# 16n.net
KiCad netlist of a schematic drawn in EAGLE
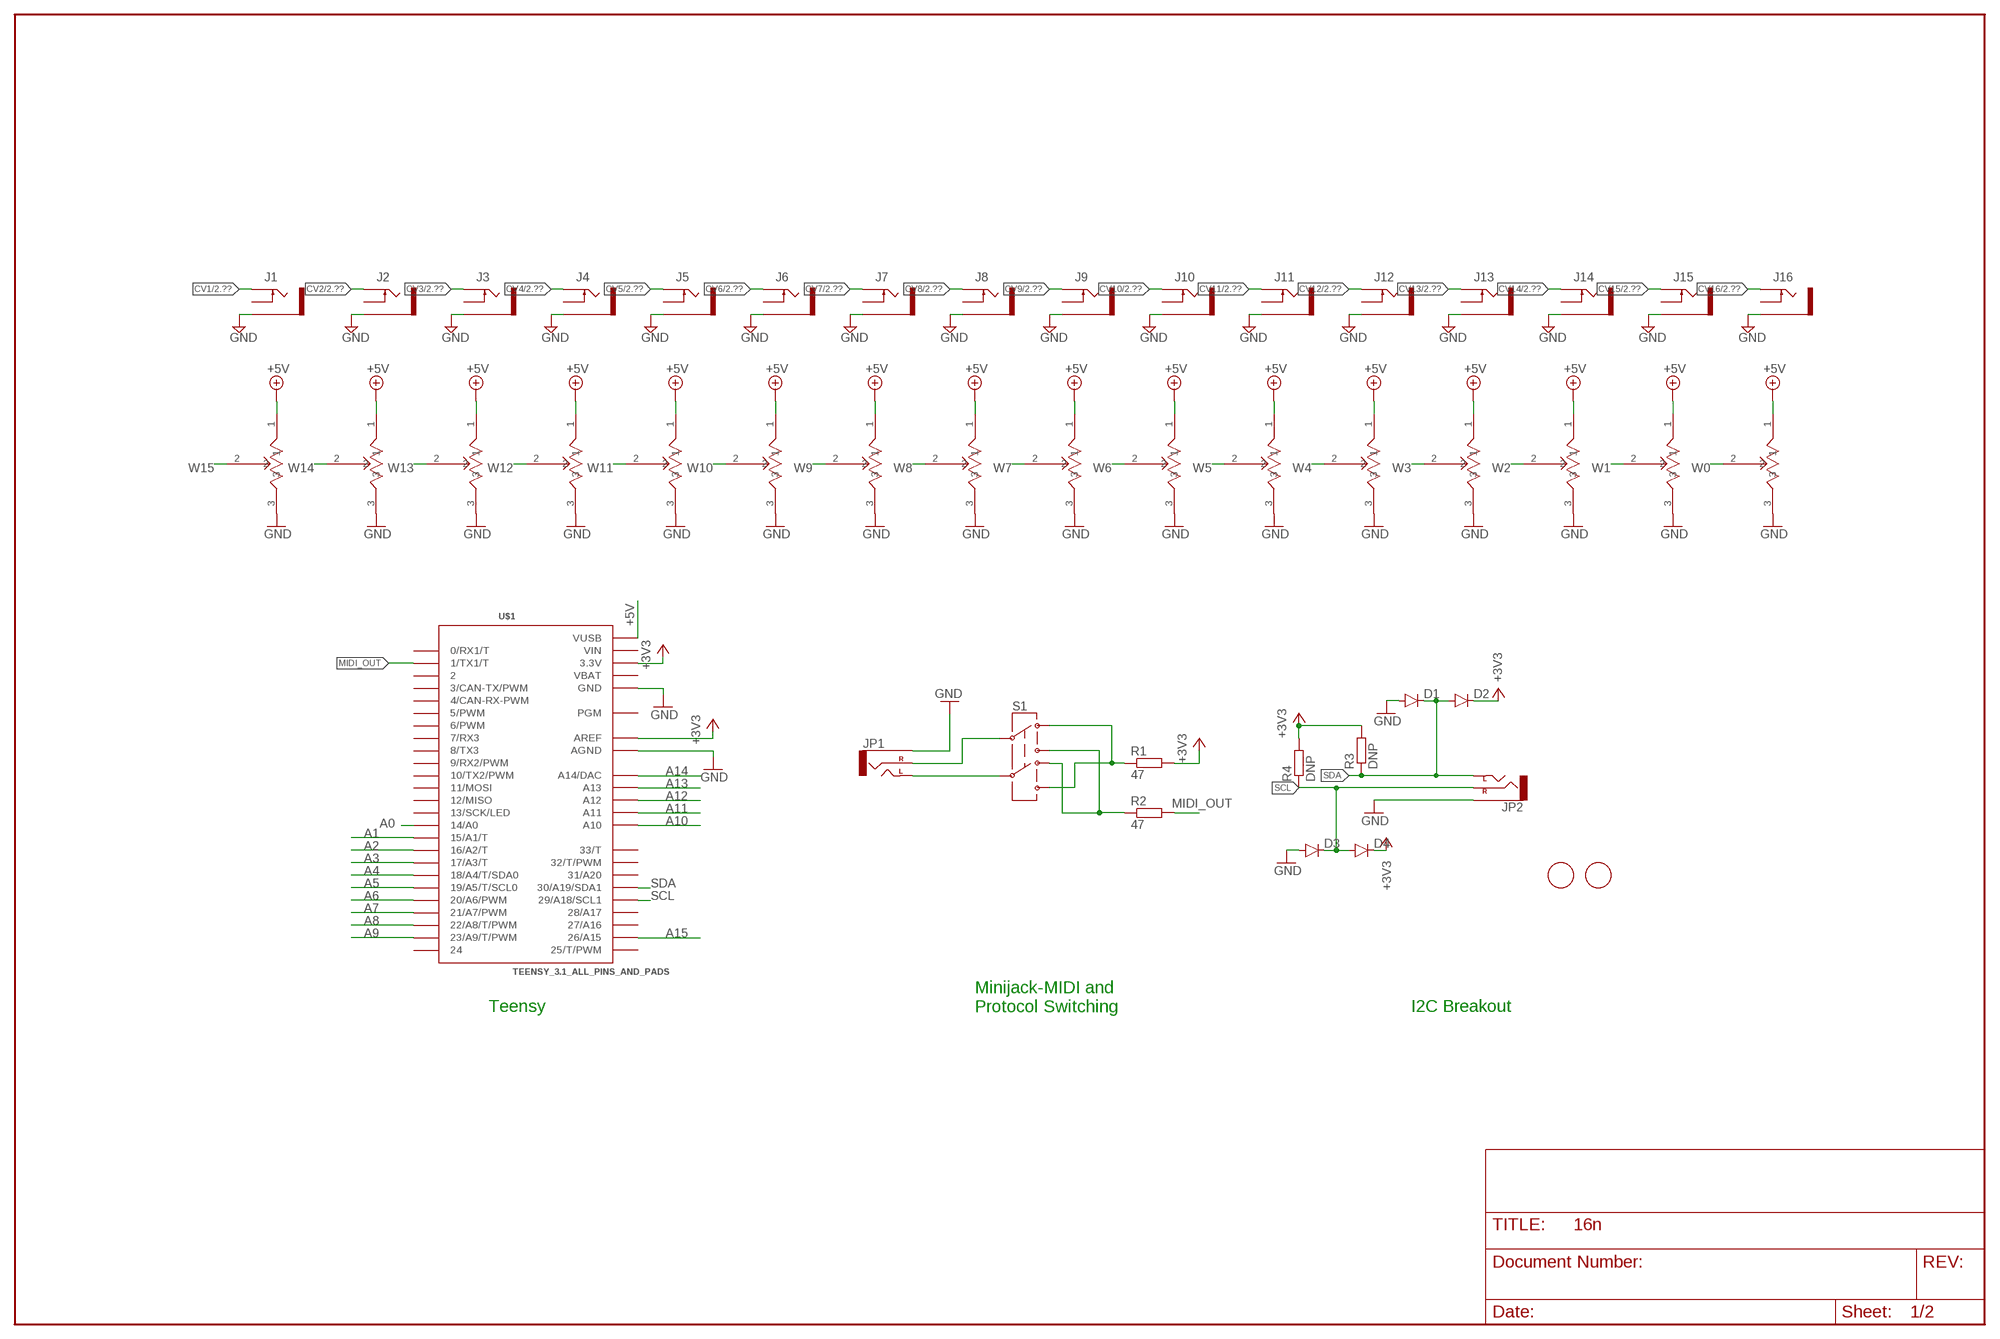
[diagram p0: schematic, sheet 1]
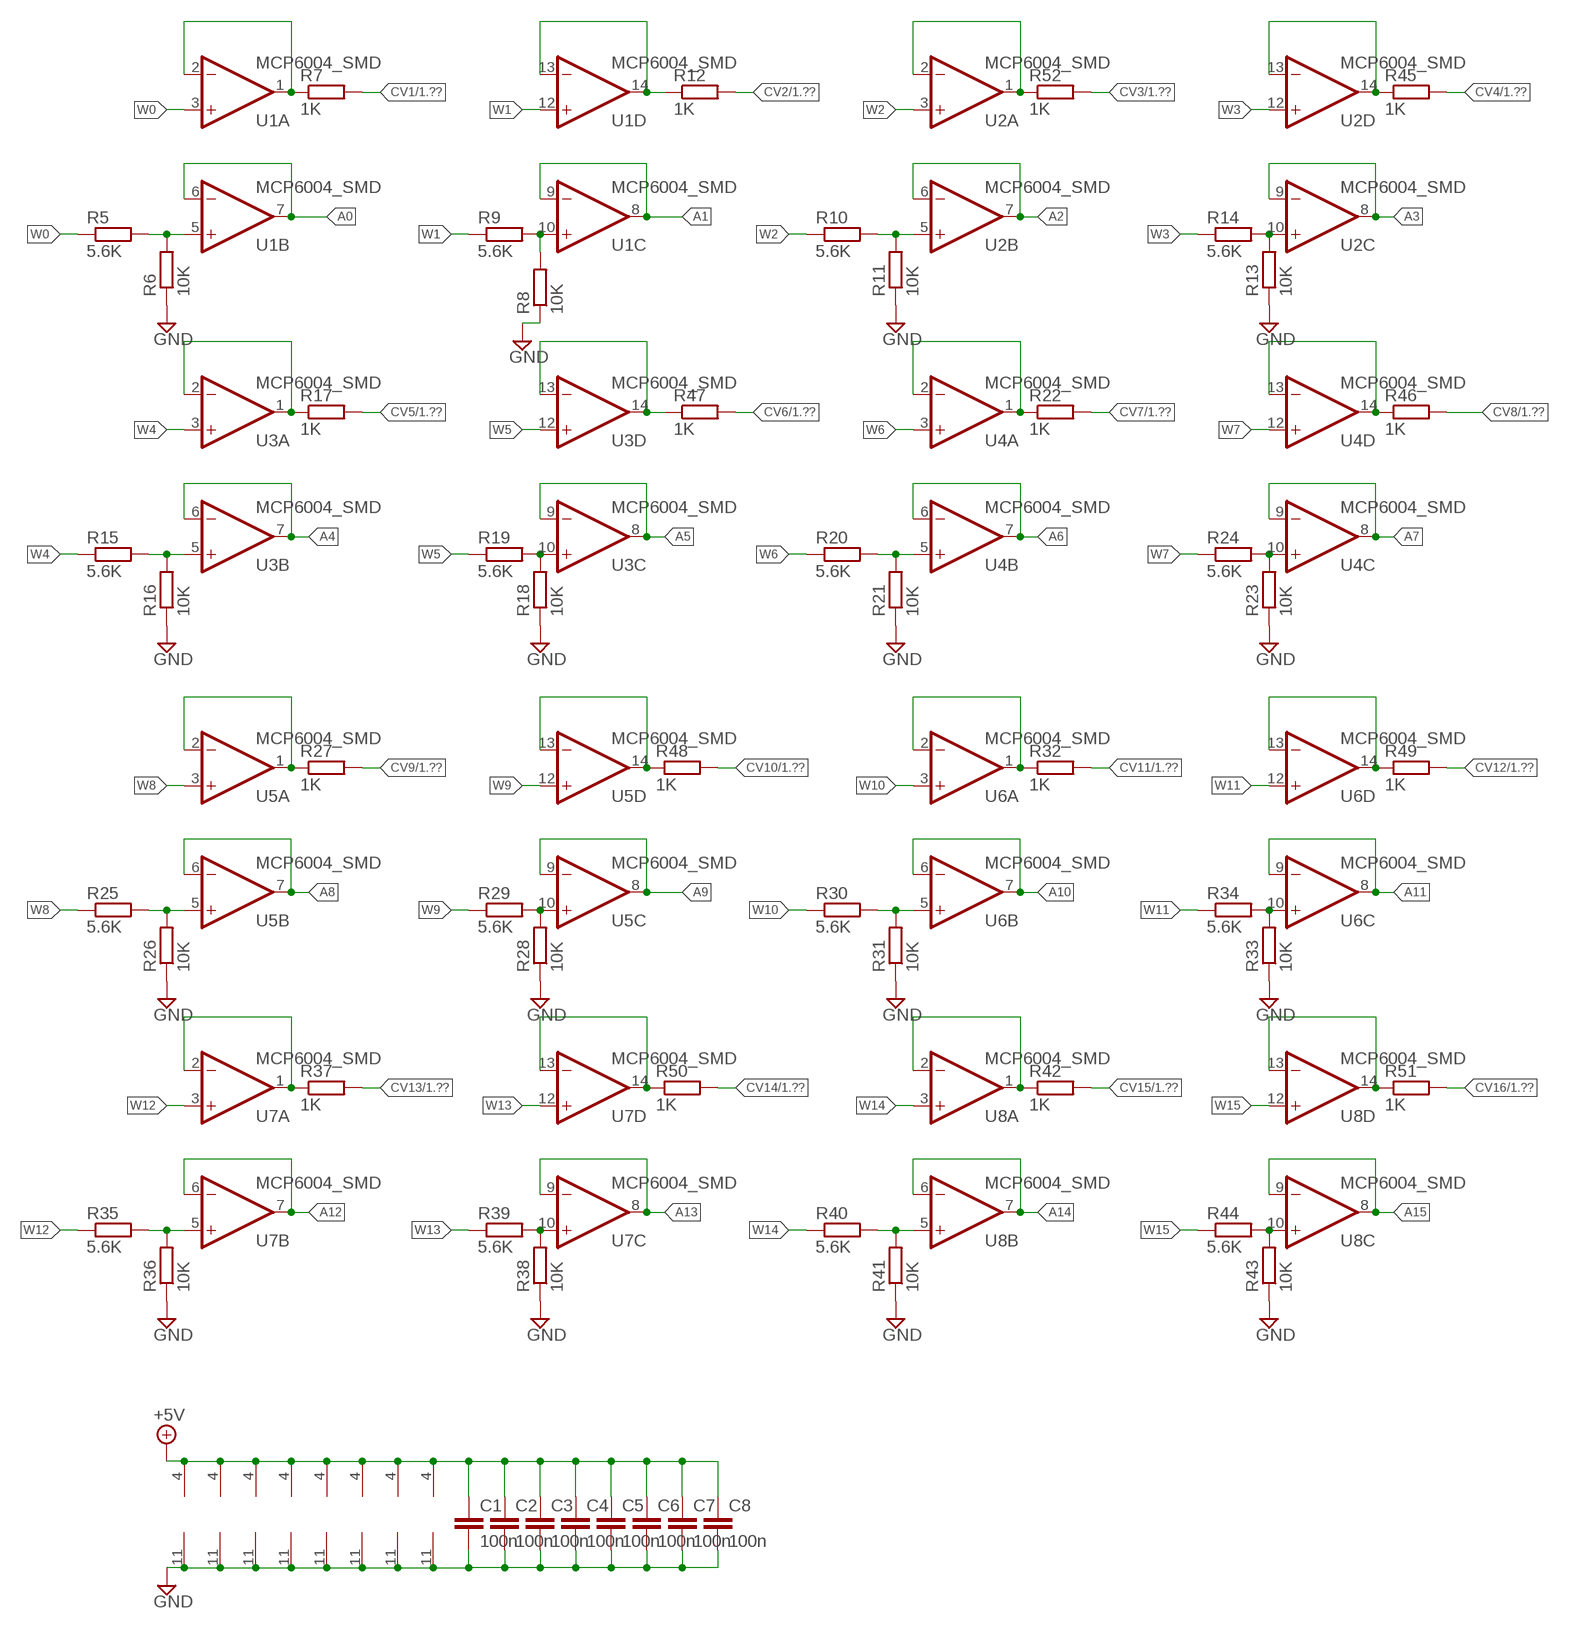
[diagram p1: schematic, sheet 2]

(export (version "E")
  (design (tool "Eeschema 10.0.6"))
  (components
    (comp (ref "D1")
      (value "DIODESOD123")
      (footprint "eagle-import:SOD-123")
      (libsource (lib "eagle-import") (part "DIODESOD123"))
    )
    (comp (ref "D2")
      (value "DIODESOD123")
      (footprint "eagle-import:SOD-123")
      (libsource (lib "eagle-import") (part "DIODESOD123"))
    )
    (comp (ref "D3")
      (value "DIODESOD123")
      (footprint "eagle-import:SOD-123")
      (libsource (lib "eagle-import") (part "DIODESOD123"))
    )
    (comp (ref "D4")
      (value "DIODESOD123")
      (footprint "eagle-import:SOD-123")
      (libsource (lib "eagle-import") (part "DIODESOD123"))
    )
    (comp (ref "FID1")
      (value "FIDUCIAL")
      (footprint "eagle-import:FIDUCIAL_1MM")
      (libsource (lib "eagle-import") (part "FIDUCIAL"))
    )
    (comp (ref "FID2")
      (value "FIDUCIAL")
      (footprint "eagle-import:FIDUCIAL_1MM")
      (libsource (lib "eagle-import") (part "FIDUCIAL"))
    )
    (comp (ref "J1")
      (value "PJ302M")
      (footprint "eagle-import:PJ302M")
      (libsource (lib "eagle-import") (part "PJ302M"))
    )
    (comp (ref "J2")
      (value "PJ302M")
      (footprint "eagle-import:PJ302M")
      (libsource (lib "eagle-import") (part "PJ302M"))
    )
    (comp (ref "J3")
      (value "PJ302M")
      (footprint "eagle-import:PJ302M")
      (libsource (lib "eagle-import") (part "PJ302M"))
    )
    (comp (ref "J4")
      (value "PJ302M")
      (footprint "eagle-import:PJ302M")
      (libsource (lib "eagle-import") (part "PJ302M"))
    )
    (comp (ref "J5")
      (value "PJ302M")
      (footprint "eagle-import:PJ302M")
      (libsource (lib "eagle-import") (part "PJ302M"))
    )
    (comp (ref "J6")
      (value "PJ302M")
      (footprint "eagle-import:PJ302M")
      (libsource (lib "eagle-import") (part "PJ302M"))
    )
    (comp (ref "J7")
      (value "PJ302M")
      (footprint "eagle-import:PJ302M")
      (libsource (lib "eagle-import") (part "PJ302M"))
    )
    (comp (ref "J8")
      (value "PJ302M")
      (footprint "eagle-import:PJ302M")
      (libsource (lib "eagle-import") (part "PJ302M"))
    )
    (comp (ref "J9")
      (value "PJ302M")
      (footprint "eagle-import:PJ302M")
      (libsource (lib "eagle-import") (part "PJ302M"))
    )
    (comp (ref "J10")
      (value "PJ302M")
      (footprint "eagle-import:PJ302M")
      (libsource (lib "eagle-import") (part "PJ302M"))
    )
    (comp (ref "J11")
      (value "PJ302M")
      (footprint "eagle-import:PJ302M")
      (libsource (lib "eagle-import") (part "PJ302M"))
    )
    (comp (ref "J12")
      (value "PJ302M")
      (footprint "eagle-import:PJ302M")
      (libsource (lib "eagle-import") (part "PJ302M"))
    )
    (comp (ref "J13")
      (value "PJ302M")
      (footprint "eagle-import:PJ302M")
      (libsource (lib "eagle-import") (part "PJ302M"))
    )
    (comp (ref "J14")
      (value "PJ302M")
      (footprint "eagle-import:PJ302M")
      (libsource (lib "eagle-import") (part "PJ302M"))
    )
    (comp (ref "J15")
      (value "PJ302M")
      (footprint "eagle-import:PJ302M")
      (libsource (lib "eagle-import") (part "PJ302M"))
    )
    (comp (ref "J16")
      (value "PJ302M")
      (footprint "eagle-import:PJ302M")
      (libsource (lib "eagle-import") (part "PJ302M"))
    )
    (comp (ref "JP1")
      (value "AUDIO-JACKPTH")
      (footprint "eagle-import:AUDIO-JACK")
      (libsource (lib "eagle-import") (part "AUDIO-JACKPTH"))
    )
    (comp (ref "JP2")
      (value "AUDIO-JACKPTH")
      (footprint "eagle-import:AUDIO-JACK")
      (libsource (lib "eagle-import") (part "AUDIO-JACKPTH"))
    )
    (comp (ref "R1")
      (value "47")
      (footprint "eagle-import:R0805")
      (libsource (lib "eagle-import") (part "R-EU_R0805"))
    )
    (comp (ref "R2")
      (value "47")
      (footprint "eagle-import:R0805")
      (libsource (lib "eagle-import") (part "R-EU_R0805"))
    )
    (comp (ref "R3")
      (value "DNP")
      (footprint "eagle-import:R0805")
      (libsource (lib "eagle-import") (part "R-EU_R0805"))
    )
    (comp (ref "R4")
      (value "DNP")
      (footprint "eagle-import:R0805")
      (libsource (lib "eagle-import") (part "R-EU_R0805"))
    )
    (comp (ref "S1")
      (value "SWITCH-DPDTEG2211")
      (footprint "eagle-import:EG2211")
      (libsource (lib "eagle-import") (part "SWITCH-DPDTEG2211"))
    )
    (comp (ref "U$1")
      (value "TEENSY_3.1_ALL_PINS_AND_PADS")
      (footprint "eagle-import:TEENSY_3.1_ALLPINS")
      (libsource (lib "eagle-import") (part "TEENSY_3.1_ALL_PINS_AND_PADS"))
    )
    (comp (ref "U$2")
      (value "SLIDEPOT-ALPS-60MM")
      (footprint "eagle-import:RS6011SP600")
      (libsource (lib "eagle-import") (part "SLIDEPOT-ALPS-60MM"))
    )
    (comp (ref "U$3")
      (value "SLIDEPOT-ALPS-60MM")
      (footprint "eagle-import:RS6011SP600")
      (libsource (lib "eagle-import") (part "SLIDEPOT-ALPS-60MM"))
    )
    (comp (ref "U$4")
      (value "SLIDEPOT-ALPS-60MM")
      (footprint "eagle-import:RS6011SP600")
      (libsource (lib "eagle-import") (part "SLIDEPOT-ALPS-60MM"))
    )
    (comp (ref "U$5")
      (value "SLIDEPOT-ALPS-60MM")
      (footprint "eagle-import:RS6011SP600")
      (libsource (lib "eagle-import") (part "SLIDEPOT-ALPS-60MM"))
    )
    (comp (ref "U$6")
      (value "SLIDEPOT-ALPS-60MM")
      (footprint "eagle-import:RS6011SP600")
      (libsource (lib "eagle-import") (part "SLIDEPOT-ALPS-60MM"))
    )
    (comp (ref "U$7")
      (value "SLIDEPOT-ALPS-60MM")
      (footprint "eagle-import:RS6011SP600")
      (libsource (lib "eagle-import") (part "SLIDEPOT-ALPS-60MM"))
    )
    (comp (ref "U$8")
      (value "SLIDEPOT-ALPS-60MM")
      (footprint "eagle-import:RS6011SP600")
      (libsource (lib "eagle-import") (part "SLIDEPOT-ALPS-60MM"))
    )
    (comp (ref "U$9")
      (value "SLIDEPOT-ALPS-60MM")
      (footprint "eagle-import:RS6011SP600")
      (libsource (lib "eagle-import") (part "SLIDEPOT-ALPS-60MM"))
    )
    (comp (ref "U$10")
      (value "SLIDEPOT-ALPS-60MM")
      (footprint "eagle-import:RS6011SP600")
      (libsource (lib "eagle-import") (part "SLIDEPOT-ALPS-60MM"))
    )
    (comp (ref "U$11")
      (value "SLIDEPOT-ALPS-60MM")
      (footprint "eagle-import:RS6011SP600")
      (libsource (lib "eagle-import") (part "SLIDEPOT-ALPS-60MM"))
    )
    (comp (ref "U$12")
      (value "SLIDEPOT-ALPS-60MM")
      (footprint "eagle-import:RS6011SP600")
      (libsource (lib "eagle-import") (part "SLIDEPOT-ALPS-60MM"))
    )
    (comp (ref "U$13")
      (value "SLIDEPOT-ALPS-60MM")
      (footprint "eagle-import:RS6011SP600")
      (libsource (lib "eagle-import") (part "SLIDEPOT-ALPS-60MM"))
    )
    (comp (ref "U$14")
      (value "SLIDEPOT-ALPS-60MM")
      (footprint "eagle-import:RS6011SP600")
      (libsource (lib "eagle-import") (part "SLIDEPOT-ALPS-60MM"))
    )
    (comp (ref "U$15")
      (value "SLIDEPOT-ALPS-60MM")
      (footprint "eagle-import:RS6011SP600")
      (libsource (lib "eagle-import") (part "SLIDEPOT-ALPS-60MM"))
    )
    (comp (ref "U$16")
      (value "SLIDEPOT-ALPS-60MM")
      (footprint "eagle-import:RS6011SP600")
      (libsource (lib "eagle-import") (part "SLIDEPOT-ALPS-60MM"))
    )
    (comp (ref "U$17")
      (value "SLIDEPOT-ALPS-60MM")
      (footprint "eagle-import:RS6011SP600")
      (libsource (lib "eagle-import") (part "SLIDEPOT-ALPS-60MM"))
    )
    (comp (ref "C1")
      (value "100n")
      (footprint "eagle-import:C0805")
      (libsource (lib "eagle-import") (part "C-EUC0805"))
    )
    (comp (ref "C2")
      (value "100n")
      (footprint "eagle-import:C0805")
      (libsource (lib "eagle-import") (part "C-EUC0805"))
    )
    (comp (ref "C3")
      (value "100n")
      (footprint "eagle-import:C0805")
      (libsource (lib "eagle-import") (part "C-EUC0805"))
    )
    (comp (ref "C4")
      (value "100n")
      (footprint "eagle-import:C0805")
      (libsource (lib "eagle-import") (part "C-EUC0805"))
    )
    (comp (ref "C5")
      (value "100n")
      (footprint "eagle-import:C0805")
      (libsource (lib "eagle-import") (part "C-EUC0805"))
    )
    (comp (ref "C6")
      (value "100n")
      (footprint "eagle-import:C0805")
      (libsource (lib "eagle-import") (part "C-EUC0805"))
    )
    (comp (ref "C7")
      (value "100n")
      (footprint "eagle-import:C0805")
      (libsource (lib "eagle-import") (part "C-EUC0805"))
    )
    (comp (ref "C8")
      (value "100n")
      (footprint "eagle-import:C0805")
      (libsource (lib "eagle-import") (part "C-EUC0805"))
    )
    (comp (ref "R5")
      (value "5.6K")
      (footprint "eagle-import:R0805")
      (libsource (lib "eagle-import") (part "R-EU_R0805"))
    )
    (comp (ref "R6")
      (value "10K")
      (footprint "eagle-import:R0805")
      (libsource (lib "eagle-import") (part "R-EU_R0805"))
    )
    (comp (ref "R7")
      (value "1K")
      (footprint "eagle-import:R0805")
      (libsource (lib "eagle-import") (part "R-EU_R0805"))
    )
    (comp (ref "R8")
      (value "10K")
      (footprint "eagle-import:R0805")
      (libsource (lib "eagle-import") (part "R-EU_R0805"))
    )
    (comp (ref "R9")
      (value "5.6K")
      (footprint "eagle-import:R0805")
      (libsource (lib "eagle-import") (part "R-EU_R0805"))
    )
    (comp (ref "R10")
      (value "5.6K")
      (footprint "eagle-import:R0805")
      (libsource (lib "eagle-import") (part "R-EU_R0805"))
    )
    (comp (ref "R11")
      (value "10K")
      (footprint "eagle-import:R0805")
      (libsource (lib "eagle-import") (part "R-EU_R0805"))
    )
    (comp (ref "R12")
      (value "1K")
      (footprint "eagle-import:R0805")
      (libsource (lib "eagle-import") (part "R-EU_R0805"))
    )
    (comp (ref "R13")
      (value "10K")
      (footprint "eagle-import:R0805")
      (libsource (lib "eagle-import") (part "R-EU_R0805"))
    )
    (comp (ref "R14")
      (value "5.6K")
      (footprint "eagle-import:R0805")
      (libsource (lib "eagle-import") (part "R-EU_R0805"))
    )
    (comp (ref "R15")
      (value "5.6K")
      (footprint "eagle-import:R0805")
      (libsource (lib "eagle-import") (part "R-EU_R0805"))
    )
    (comp (ref "R16")
      (value "10K")
      (footprint "eagle-import:R0805")
      (libsource (lib "eagle-import") (part "R-EU_R0805"))
    )
    (comp (ref "R17")
      (value "1K")
      (footprint "eagle-import:R0805")
      (libsource (lib "eagle-import") (part "R-EU_R0805"))
    )
    (comp (ref "R18")
      (value "10K")
      (footprint "eagle-import:R0805")
      (libsource (lib "eagle-import") (part "R-EU_R0805"))
    )
    (comp (ref "R19")
      (value "5.6K")
      (footprint "eagle-import:R0805")
      (libsource (lib "eagle-import") (part "R-EU_R0805"))
    )
    (comp (ref "R20")
      (value "5.6K")
      (footprint "eagle-import:R0805")
      (libsource (lib "eagle-import") (part "R-EU_R0805"))
    )
    (comp (ref "R21")
      (value "10K")
      (footprint "eagle-import:R0805")
      (libsource (lib "eagle-import") (part "R-EU_R0805"))
    )
    (comp (ref "R22")
      (value "1K")
      (footprint "eagle-import:R0805")
      (libsource (lib "eagle-import") (part "R-EU_R0805"))
    )
    (comp (ref "R23")
      (value "10K")
      (footprint "eagle-import:R0805")
      (libsource (lib "eagle-import") (part "R-EU_R0805"))
    )
    (comp (ref "R24")
      (value "5.6K")
      (footprint "eagle-import:R0805")
      (libsource (lib "eagle-import") (part "R-EU_R0805"))
    )
    (comp (ref "R25")
      (value "5.6K")
      (footprint "eagle-import:R0805")
      (libsource (lib "eagle-import") (part "R-EU_R0805"))
    )
    (comp (ref "R26")
      (value "10K")
      (footprint "eagle-import:R0805")
      (libsource (lib "eagle-import") (part "R-EU_R0805"))
    )
    (comp (ref "R27")
      (value "1K")
      (footprint "eagle-import:R0805")
      (libsource (lib "eagle-import") (part "R-EU_R0805"))
    )
    (comp (ref "R28")
      (value "10K")
      (footprint "eagle-import:R0805")
      (libsource (lib "eagle-import") (part "R-EU_R0805"))
    )
    (comp (ref "R29")
      (value "5.6K")
      (footprint "eagle-import:R0805")
      (libsource (lib "eagle-import") (part "R-EU_R0805"))
    )
    (comp (ref "R30")
      (value "5.6K")
      (footprint "eagle-import:R0805")
      (libsource (lib "eagle-import") (part "R-EU_R0805"))
    )
    (comp (ref "R31")
      (value "10K")
      (footprint "eagle-import:R0805")
      (libsource (lib "eagle-import") (part "R-EU_R0805"))
    )
    (comp (ref "R32")
      (value "1K")
      (footprint "eagle-import:R0805")
      (libsource (lib "eagle-import") (part "R-EU_R0805"))
    )
    (comp (ref "R33")
      (value "10K")
      (footprint "eagle-import:R0805")
      (libsource (lib "eagle-import") (part "R-EU_R0805"))
    )
    (comp (ref "R34")
      (value "5.6K")
      (footprint "eagle-import:R0805")
      (libsource (lib "eagle-import") (part "R-EU_R0805"))
    )
    (comp (ref "R35")
      (value "5.6K")
      (footprint "eagle-import:R0805")
      (libsource (lib "eagle-import") (part "R-EU_R0805"))
    )
    (comp (ref "R36")
      (value "10K")
      (footprint "eagle-import:R0805")
      (libsource (lib "eagle-import") (part "R-EU_R0805"))
    )
    (comp (ref "R37")
      (value "1K")
      (footprint "eagle-import:R0805")
      (libsource (lib "eagle-import") (part "R-EU_R0805"))
    )
    (comp (ref "R38")
      (value "10K")
      (footprint "eagle-import:R0805")
      (libsource (lib "eagle-import") (part "R-EU_R0805"))
    )
    (comp (ref "R39")
      (value "5.6K")
      (footprint "eagle-import:R0805")
      (libsource (lib "eagle-import") (part "R-EU_R0805"))
    )
    (comp (ref "R40")
      (value "5.6K")
      (footprint "eagle-import:R0805")
      (libsource (lib "eagle-import") (part "R-EU_R0805"))
    )
    (comp (ref "R41")
      (value "10K")
      (footprint "eagle-import:R0805")
      (libsource (lib "eagle-import") (part "R-EU_R0805"))
    )
    (comp (ref "R42")
      (value "1K")
      (footprint "eagle-import:R0805")
      (libsource (lib "eagle-import") (part "R-EU_R0805"))
    )
    (comp (ref "R43")
      (value "10K")
      (footprint "eagle-import:R0805")
      (libsource (lib "eagle-import") (part "R-EU_R0805"))
    )
    (comp (ref "R44")
      (value "5.6K")
      (footprint "eagle-import:R0805")
      (libsource (lib "eagle-import") (part "R-EU_R0805"))
    )
    (comp (ref "R45")
      (value "1K")
      (footprint "eagle-import:R0805")
      (libsource (lib "eagle-import") (part "R-EU_R0805"))
    )
    (comp (ref "R46")
      (value "1K")
      (footprint "eagle-import:R0805")
      (libsource (lib "eagle-import") (part "R-EU_R0805"))
    )
    (comp (ref "R47")
      (value "1K")
      (footprint "eagle-import:R0805")
      (libsource (lib "eagle-import") (part "R-EU_R0805"))
    )
    (comp (ref "R48")
      (value "1K")
      (footprint "eagle-import:R0805")
      (libsource (lib "eagle-import") (part "R-EU_R0805"))
    )
    (comp (ref "R49")
      (value "1K")
      (footprint "eagle-import:R0805")
      (libsource (lib "eagle-import") (part "R-EU_R0805"))
    )
    (comp (ref "R50")
      (value "1K")
      (footprint "eagle-import:R0805")
      (libsource (lib "eagle-import") (part "R-EU_R0805"))
    )
    (comp (ref "R51")
      (value "1K")
      (footprint "eagle-import:R0805")
      (libsource (lib "eagle-import") (part "R-EU_R0805"))
    )
    (comp (ref "R52")
      (value "1K")
      (footprint "eagle-import:R0805")
      (libsource (lib "eagle-import") (part "R-EU_R0805"))
    )
    (comp (ref "U1")
      (value "MCP6004_SMD")
      (footprint "eagle-import:SO14")
      (libsource (lib "eagle-import") (part "MCP6004_SMD"))
    )
    (comp (ref "U2")
      (value "MCP6004_SMD")
      (footprint "eagle-import:SO14")
      (libsource (lib "eagle-import") (part "MCP6004_SMD"))
    )
    (comp (ref "U3")
      (value "MCP6004_SMD")
      (footprint "eagle-import:SO14")
      (libsource (lib "eagle-import") (part "MCP6004_SMD"))
    )
    (comp (ref "U4")
      (value "MCP6004_SMD")
      (footprint "eagle-import:SO14")
      (libsource (lib "eagle-import") (part "MCP6004_SMD"))
    )
    (comp (ref "U5")
      (value "MCP6004_SMD")
      (footprint "eagle-import:SO14")
      (libsource (lib "eagle-import") (part "MCP6004_SMD"))
    )
    (comp (ref "U6")
      (value "MCP6004_SMD")
      (footprint "eagle-import:SO14")
      (libsource (lib "eagle-import") (part "MCP6004_SMD"))
    )
    (comp (ref "U7")
      (value "MCP6004_SMD")
      (footprint "eagle-import:SO14")
      (libsource (lib "eagle-import") (part "MCP6004_SMD"))
    )
    (comp (ref "U8")
      (value "MCP6004_SMD")
      (footprint "eagle-import:SO14")
      (libsource (lib "eagle-import") (part "MCP6004_SMD"))
    )
  )
  (nets
    (net (code "1") (name "+3V3") (class "Default")
      (node (ref "D2") (pin "C") (pinfunction "C_C") (pintype "passive"))
      (node (ref "D4") (pin "C") (pinfunction "C_C") (pintype "passive"))
      (node (ref "R1") (pin "2") (pinfunction "2_2") (pintype "passive"))
      (node (ref "R3") (pin "2") (pinfunction "2_2") (pintype "passive"))
      (node (ref "R4") (pin "2") (pinfunction "2_2") (pintype "passive"))
      (node (ref "U$1") (pin "3.3V") (pinfunction "3.3V_3.3V") (pintype "power_in"))
      (node (ref "U$1") (pin "3.3V1") (pinfunction "3.3V_3.3V1") (pintype "power_in"))
      (node (ref "U$1") (pin "3.3V2") (pinfunction "3.3V_3.3V2") (pintype "power_in"))
      (node (ref "U$1") (pin "AREF") (pinfunction "AREF_AREF") (pintype "power_in"))
    )
    (net (code "2") (name "+5V") (class "Default")
      (node (ref "C1") (pin "1") (pinfunction "1_1") (pintype "passive"))
      (node (ref "C2") (pin "1") (pinfunction "1_1") (pintype "passive"))
      (node (ref "C3") (pin "1") (pinfunction "1_1") (pintype "passive"))
      (node (ref "C4") (pin "1") (pinfunction "1_1") (pintype "passive"))
      (node (ref "C5") (pin "1") (pinfunction "1_1") (pintype "passive"))
      (node (ref "C6") (pin "1") (pinfunction "1_1") (pintype "passive"))
      (node (ref "C7") (pin "1") (pinfunction "1_1") (pintype "passive"))
      (node (ref "C8") (pin "1") (pinfunction "1_1") (pintype "passive"))
      (node (ref "U$1") (pin "VUSB") (pinfunction "VUSB_VUSB") (pintype "power_in"))
      (node (ref "U$10") (pin "1") (pinfunction "1_1") (pintype "bidirectional"))
      (node (ref "U$11") (pin "1") (pinfunction "1_1") (pintype "bidirectional"))
      (node (ref "U$12") (pin "1") (pinfunction "1_1") (pintype "bidirectional"))
      (node (ref "U$13") (pin "1") (pinfunction "1_1") (pintype "bidirectional"))
      (node (ref "U$14") (pin "1") (pinfunction "1_1") (pintype "bidirectional"))
      (node (ref "U$15") (pin "1") (pinfunction "1_1") (pintype "bidirectional"))
      (node (ref "U$16") (pin "1") (pinfunction "1_1") (pintype "bidirectional"))
      (node (ref "U$17") (pin "1") (pinfunction "1_1") (pintype "bidirectional"))
      (node (ref "U$2") (pin "1") (pinfunction "1_1") (pintype "bidirectional"))
      (node (ref "U$3") (pin "1") (pinfunction "1_1") (pintype "bidirectional"))
      (node (ref "U$4") (pin "1") (pinfunction "1_1") (pintype "bidirectional"))
      (node (ref "U$5") (pin "1") (pinfunction "1_1") (pintype "bidirectional"))
      (node (ref "U$6") (pin "1") (pinfunction "1_1") (pintype "bidirectional"))
      (node (ref "U$7") (pin "1") (pinfunction "1_1") (pintype "bidirectional"))
      (node (ref "U$8") (pin "1") (pinfunction "1_1") (pintype "bidirectional"))
      (node (ref "U$9") (pin "1") (pinfunction "1_1") (pintype "bidirectional"))
      (node (ref "U1") (pin "4") (pinfunction "V+_4") (pintype "power_in"))
      (node (ref "U2") (pin "4") (pinfunction "V+_4") (pintype "power_in"))
      (node (ref "U3") (pin "4") (pinfunction "V+_4") (pintype "power_in"))
      (node (ref "U4") (pin "4") (pinfunction "V+_4") (pintype "power_in"))
      (node (ref "U5") (pin "4") (pinfunction "V+_4") (pintype "power_in"))
      (node (ref "U6") (pin "4") (pinfunction "V+_4") (pintype "power_in"))
      (node (ref "U7") (pin "4") (pinfunction "V+_4") (pintype "power_in"))
      (node (ref "U8") (pin "4") (pinfunction "V+_4") (pintype "power_in"))
    )
    (net (code "3") (name "A0") (class "Default")
      (node (ref "U$1") (pin "14/A0") (pinfunction "14/A0_14/A0") (pintype "bidirectional"))
      (node (ref "U1") (pin "6") (pinfunction "-IN_6") (pintype "input"))
      (node (ref "U1") (pin "7") (pinfunction "OUT_7") (pintype "output"))
    )
    (net (code "4") (name "A1") (class "Default")
      (node (ref "U$1") (pin "15/A1") (pinfunction "15/A1/T_15/A1") (pintype "bidirectional"))
      (node (ref "U1") (pin "8") (pinfunction "OUT_8") (pintype "output"))
      (node (ref "U1") (pin "9") (pinfunction "-IN_9") (pintype "input"))
    )
    (net (code "5") (name "A2") (class "Default")
      (node (ref "U$1") (pin "16/A2") (pinfunction "16/A2/T_16/A2") (pintype "bidirectional"))
      (node (ref "U2") (pin "6") (pinfunction "-IN_6") (pintype "input"))
      (node (ref "U2") (pin "7") (pinfunction "OUT_7") (pintype "output"))
    )
    (net (code "6") (name "A3") (class "Default")
      (node (ref "U$1") (pin "17/A3") (pinfunction "17/A3/T_17/A3") (pintype "bidirectional"))
      (node (ref "U2") (pin "8") (pinfunction "OUT_8") (pintype "output"))
      (node (ref "U2") (pin "9") (pinfunction "-IN_9") (pintype "input"))
    )
    (net (code "7") (name "A4") (class "Default")
      (node (ref "U$1") (pin "18/A4") (pinfunction "18/A4/T/SDA0_18/A4") (pintype "bidirectional"))
      (node (ref "U3") (pin "6") (pinfunction "-IN_6") (pintype "input"))
      (node (ref "U3") (pin "7") (pinfunction "OUT_7") (pintype "output"))
    )
    (net (code "8") (name "A5") (class "Default")
      (node (ref "U$1") (pin "19/A5") (pinfunction "19/A5/T/SCL0_19/A5") (pintype "bidirectional"))
      (node (ref "U3") (pin "8") (pinfunction "OUT_8") (pintype "output"))
      (node (ref "U3") (pin "9") (pinfunction "-IN_9") (pintype "input"))
    )
    (net (code "9") (name "A6") (class "Default")
      (node (ref "U$1") (pin "20/A6") (pinfunction "20/A6/PWM_20/A6") (pintype "bidirectional"))
      (node (ref "U4") (pin "6") (pinfunction "-IN_6") (pintype "input"))
      (node (ref "U4") (pin "7") (pinfunction "OUT_7") (pintype "output"))
    )
    (net (code "10") (name "A7") (class "Default")
      (node (ref "U$1") (pin "21/A7") (pinfunction "21/A7/PWM_21/A7") (pintype "bidirectional"))
      (node (ref "U4") (pin "8") (pinfunction "OUT_8") (pintype "output"))
      (node (ref "U4") (pin "9") (pinfunction "-IN_9") (pintype "input"))
    )
    (net (code "11") (name "A8") (class "Default")
      (node (ref "U$1") (pin "22/A8") (pinfunction "22/A8/T/PWM_22/A8") (pintype "bidirectional"))
      (node (ref "U5") (pin "6") (pinfunction "-IN_6") (pintype "input"))
      (node (ref "U5") (pin "7") (pinfunction "OUT_7") (pintype "output"))
    )
    (net (code "12") (name "A9") (class "Default")
      (node (ref "U$1") (pin "23/A9") (pinfunction "23/A9/T/PWM_23/A9") (pintype "bidirectional"))
      (node (ref "U5") (pin "8") (pinfunction "OUT_8") (pintype "output"))
      (node (ref "U5") (pin "9") (pinfunction "-IN_9") (pintype "input"))
    )
    (net (code "13") (name "A10") (class "Default")
      (node (ref "U$1") (pin "A10") (pinfunction "A10_A10") (pintype "bidirectional"))
      (node (ref "U6") (pin "6") (pinfunction "-IN_6") (pintype "input"))
      (node (ref "U6") (pin "7") (pinfunction "OUT_7") (pintype "output"))
    )
    (net (code "14") (name "A11") (class "Default")
      (node (ref "U$1") (pin "A11") (pinfunction "A11_A11") (pintype "bidirectional"))
      (node (ref "U6") (pin "8") (pinfunction "OUT_8") (pintype "output"))
      (node (ref "U6") (pin "9") (pinfunction "-IN_9") (pintype "input"))
    )
    (net (code "15") (name "A12") (class "Default")
      (node (ref "U$1") (pin "A12") (pinfunction "A12_A12") (pintype "bidirectional"))
      (node (ref "U7") (pin "6") (pinfunction "-IN_6") (pintype "input"))
      (node (ref "U7") (pin "7") (pinfunction "OUT_7") (pintype "output"))
    )
    (net (code "16") (name "A13") (class "Default")
      (node (ref "U$1") (pin "A13") (pinfunction "A13_A13") (pintype "bidirectional"))
      (node (ref "U7") (pin "8") (pinfunction "OUT_8") (pintype "output"))
      (node (ref "U7") (pin "9") (pinfunction "-IN_9") (pintype "input"))
    )
    (net (code "17") (name "A14") (class "Default")
      (node (ref "U$1") (pin "A14") (pinfunction "A14/DAC_A14") (pintype "bidirectional"))
      (node (ref "U8") (pin "6") (pinfunction "-IN_6") (pintype "input"))
      (node (ref "U8") (pin "7") (pinfunction "OUT_7") (pintype "output"))
    )
    (net (code "18") (name "A15") (class "Default")
      (node (ref "U$1") (pin "26") (pinfunction "26/A15_26") (pintype "bidirectional"))
      (node (ref "U8") (pin "8") (pinfunction "OUT_8") (pintype "output"))
      (node (ref "U8") (pin "9") (pinfunction "-IN_9") (pintype "input"))
    )
    (net (code "19") (name "CV1") (class "Default")
      (node (ref "J1") (pin "TIP") (pinfunction "TIP_TIP") (pintype "passive"))
      (node (ref "R7") (pin "2") (pinfunction "2_2") (pintype "passive"))
    )
    (net (code "20") (name "CV2") (class "Default")
      (node (ref "J2") (pin "TIP") (pinfunction "TIP_TIP") (pintype "passive"))
      (node (ref "R12") (pin "2") (pinfunction "2_2") (pintype "passive"))
    )
    (net (code "21") (name "CV3") (class "Default")
      (node (ref "J3") (pin "TIP") (pinfunction "TIP_TIP") (pintype "passive"))
      (node (ref "R52") (pin "2") (pinfunction "2_2") (pintype "passive"))
    )
    (net (code "22") (name "CV4") (class "Default")
      (node (ref "J4") (pin "TIP") (pinfunction "TIP_TIP") (pintype "passive"))
      (node (ref "R45") (pin "2") (pinfunction "2_2") (pintype "passive"))
    )
    (net (code "23") (name "CV5") (class "Default")
      (node (ref "J5") (pin "TIP") (pinfunction "TIP_TIP") (pintype "passive"))
      (node (ref "R17") (pin "2") (pinfunction "2_2") (pintype "passive"))
    )
    (net (code "24") (name "CV6") (class "Default")
      (node (ref "J6") (pin "TIP") (pinfunction "TIP_TIP") (pintype "passive"))
      (node (ref "R47") (pin "2") (pinfunction "2_2") (pintype "passive"))
    )
    (net (code "25") (name "CV7") (class "Default")
      (node (ref "J7") (pin "TIP") (pinfunction "TIP_TIP") (pintype "passive"))
      (node (ref "R22") (pin "2") (pinfunction "2_2") (pintype "passive"))
    )
    (net (code "26") (name "CV8") (class "Default")
      (node (ref "J8") (pin "TIP") (pinfunction "TIP_TIP") (pintype "passive"))
      (node (ref "R46") (pin "2") (pinfunction "2_2") (pintype "passive"))
    )
    (net (code "27") (name "CV9") (class "Default")
      (node (ref "J9") (pin "TIP") (pinfunction "TIP_TIP") (pintype "passive"))
      (node (ref "R27") (pin "2") (pinfunction "2_2") (pintype "passive"))
    )
    (net (code "28") (name "CV10") (class "Default")
      (node (ref "J10") (pin "TIP") (pinfunction "TIP_TIP") (pintype "passive"))
      (node (ref "R48") (pin "2") (pinfunction "2_2") (pintype "passive"))
    )
    (net (code "29") (name "CV11") (class "Default")
      (node (ref "J11") (pin "TIP") (pinfunction "TIP_TIP") (pintype "passive"))
      (node (ref "R32") (pin "2") (pinfunction "2_2") (pintype "passive"))
    )
    (net (code "30") (name "CV12") (class "Default")
      (node (ref "J12") (pin "TIP") (pinfunction "TIP_TIP") (pintype "passive"))
      (node (ref "R49") (pin "2") (pinfunction "2_2") (pintype "passive"))
    )
    (net (code "31") (name "CV13") (class "Default")
      (node (ref "J13") (pin "TIP") (pinfunction "TIP_TIP") (pintype "passive"))
      (node (ref "R37") (pin "2") (pinfunction "2_2") (pintype "passive"))
    )
    (net (code "32") (name "CV14") (class "Default")
      (node (ref "J14") (pin "TIP") (pinfunction "TIP_TIP") (pintype "passive"))
      (node (ref "R50") (pin "2") (pinfunction "2_2") (pintype "passive"))
    )
    (net (code "33") (name "CV15") (class "Default")
      (node (ref "J15") (pin "TIP") (pinfunction "TIP_TIP") (pintype "passive"))
      (node (ref "R42") (pin "2") (pinfunction "2_2") (pintype "passive"))
    )
    (net (code "34") (name "CV16") (class "Default")
      (node (ref "J16") (pin "TIP") (pinfunction "TIP_TIP") (pintype "passive"))
      (node (ref "R51") (pin "2") (pinfunction "2_2") (pintype "passive"))
    )
    (net (code "35") (name "GND") (class "Default")
      (node (ref "C1") (pin "2") (pinfunction "2_2") (pintype "passive"))
      (node (ref "C2") (pin "2") (pinfunction "2_2") (pintype "passive"))
      (node (ref "C3") (pin "2") (pinfunction "2_2") (pintype "passive"))
      (node (ref "C4") (pin "2") (pinfunction "2_2") (pintype "passive"))
      (node (ref "C5") (pin "2") (pinfunction "2_2") (pintype "passive"))
      (node (ref "C6") (pin "2") (pinfunction "2_2") (pintype "passive"))
      (node (ref "C7") (pin "2") (pinfunction "2_2") (pintype "passive"))
      (node (ref "C8") (pin "2") (pinfunction "2_2") (pintype "passive"))
      (node (ref "D1") (pin "A") (pinfunction "A_A") (pintype "passive"))
      (node (ref "D3") (pin "A") (pinfunction "A_A") (pintype "passive"))
      (node (ref "J1") (pin "GND") (pinfunction "SLEEVE_GND") (pintype "passive"))
      (node (ref "J10") (pin "GND") (pinfunction "SLEEVE_GND") (pintype "passive"))
      (node (ref "J11") (pin "GND") (pinfunction "SLEEVE_GND") (pintype "passive"))
      (node (ref "J12") (pin "GND") (pinfunction "SLEEVE_GND") (pintype "passive"))
      (node (ref "J13") (pin "GND") (pinfunction "SLEEVE_GND") (pintype "passive"))
      (node (ref "J14") (pin "GND") (pinfunction "SLEEVE_GND") (pintype "passive"))
      (node (ref "J15") (pin "GND") (pinfunction "SLEEVE_GND") (pintype "passive"))
      (node (ref "J16") (pin "GND") (pinfunction "SLEEVE_GND") (pintype "passive"))
      (node (ref "J2") (pin "GND") (pinfunction "SLEEVE_GND") (pintype "passive"))
      (node (ref "J3") (pin "GND") (pinfunction "SLEEVE_GND") (pintype "passive"))
      (node (ref "J4") (pin "GND") (pinfunction "SLEEVE_GND") (pintype "passive"))
      (node (ref "J5") (pin "GND") (pinfunction "SLEEVE_GND") (pintype "passive"))
      (node (ref "J6") (pin "GND") (pinfunction "SLEEVE_GND") (pintype "passive"))
      (node (ref "J7") (pin "GND") (pinfunction "SLEEVE_GND") (pintype "passive"))
      (node (ref "J8") (pin "GND") (pinfunction "SLEEVE_GND") (pintype "passive"))
      (node (ref "J9") (pin "GND") (pinfunction "SLEEVE_GND") (pintype "passive"))
      (node (ref "JP1") (pin "SLEEVE") (pinfunction "SLEEVE_SLEEVE") (pintype "bidirectional"))
      (node (ref "JP2") (pin "SLEEVE") (pinfunction "SLEEVE_SLEEVE") (pintype "bidirectional"))
      (node (ref "R11") (pin "1") (pinfunction "1_1") (pintype "passive"))
      (node (ref "R13") (pin "1") (pinfunction "1_1") (pintype "passive"))
      (node (ref "R16") (pin "1") (pinfunction "1_1") (pintype "passive"))
      (node (ref "R18") (pin "1") (pinfunction "1_1") (pintype "passive"))
      (node (ref "R21") (pin "1") (pinfunction "1_1") (pintype "passive"))
      (node (ref "R23") (pin "1") (pinfunction "1_1") (pintype "passive"))
      (node (ref "R26") (pin "1") (pinfunction "1_1") (pintype "passive"))
      (node (ref "R28") (pin "1") (pinfunction "1_1") (pintype "passive"))
      (node (ref "R31") (pin "1") (pinfunction "1_1") (pintype "passive"))
      (node (ref "R33") (pin "1") (pinfunction "1_1") (pintype "passive"))
      (node (ref "R36") (pin "1") (pinfunction "1_1") (pintype "passive"))
      (node (ref "R38") (pin "1") (pinfunction "1_1") (pintype "passive"))
      (node (ref "R41") (pin "1") (pinfunction "1_1") (pintype "passive"))
      (node (ref "R43") (pin "1") (pinfunction "1_1") (pintype "passive"))
      (node (ref "R6") (pin "1") (pinfunction "1_1") (pintype "passive"))
      (node (ref "R8") (pin "1") (pinfunction "1_1") (pintype "passive"))
      (node (ref "U$1") (pin "AGND") (pinfunction "AGND_AGND") (pintype "power_in"))
      (node (ref "U$1") (pin "GND") (pinfunction "GND_GND") (pintype "power_in"))
      (node (ref "U$1") (pin "GND1") (pinfunction "GND_GND1") (pintype "power_in"))
      (node (ref "U$1") (pin "GND2") (pinfunction "GND_GND2") (pintype "power_in"))
      (node (ref "U$10") (pin "3") (pinfunction "3_3") (pintype "bidirectional"))
      (node (ref "U$11") (pin "3") (pinfunction "3_3") (pintype "bidirectional"))
      (node (ref "U$12") (pin "3") (pinfunction "3_3") (pintype "bidirectional"))
      (node (ref "U$13") (pin "3") (pinfunction "3_3") (pintype "bidirectional"))
      (node (ref "U$14") (pin "3") (pinfunction "3_3") (pintype "bidirectional"))
      (node (ref "U$15") (pin "3") (pinfunction "3_3") (pintype "bidirectional"))
      (node (ref "U$16") (pin "3") (pinfunction "3_3") (pintype "bidirectional"))
      (node (ref "U$17") (pin "3") (pinfunction "3_3") (pintype "bidirectional"))
      (node (ref "U$2") (pin "3") (pinfunction "3_3") (pintype "bidirectional"))
      (node (ref "U$3") (pin "3") (pinfunction "3_3") (pintype "bidirectional"))
      (node (ref "U$4") (pin "3") (pinfunction "3_3") (pintype "bidirectional"))
      (node (ref "U$5") (pin "3") (pinfunction "3_3") (pintype "bidirectional"))
      (node (ref "U$6") (pin "3") (pinfunction "3_3") (pintype "bidirectional"))
      (node (ref "U$7") (pin "3") (pinfunction "3_3") (pintype "bidirectional"))
      (node (ref "U$8") (pin "3") (pinfunction "3_3") (pintype "bidirectional"))
      (node (ref "U$9") (pin "3") (pinfunction "3_3") (pintype "bidirectional"))
      (node (ref "U1") (pin "11") (pinfunction "V-_11") (pintype "power_in"))
      (node (ref "U2") (pin "11") (pinfunction "V-_11") (pintype "power_in"))
      (node (ref "U3") (pin "11") (pinfunction "V-_11") (pintype "power_in"))
      (node (ref "U4") (pin "11") (pinfunction "V-_11") (pintype "power_in"))
      (node (ref "U5") (pin "11") (pinfunction "V-_11") (pintype "power_in"))
      (node (ref "U6") (pin "11") (pinfunction "V-_11") (pintype "power_in"))
      (node (ref "U7") (pin "11") (pinfunction "V-_11") (pintype "power_in"))
      (node (ref "U8") (pin "11") (pinfunction "V-_11") (pintype "power_in"))
    )
    (net (code "36") (name "MIDI_OUT") (class "Default")
      (node (ref "R2") (pin "2") (pinfunction "2_2") (pintype "passive"))
      (node (ref "U$1") (pin "1") (pinfunction "1/TX1/T_1") (pintype "bidirectional"))
    )
    (net (code "37") (name "Net-(JP1-LEFT)") (class "Default")
      (node (ref "JP1") (pin "TIP") (pinfunction "LEFT_TIP") (pintype "bidirectional"))
      (node (ref "S1") (pin "P2") (pinfunction "5_P2") (pintype "bidirectional"))
    )
    (net (code "38") (name "Net-(JP1-RIGHT)") (class "Default")
      (node (ref "JP1") (pin "RING") (pinfunction "RIGHT_RING") (pintype "bidirectional"))
      (node (ref "S1") (pin "P1") (pinfunction "2_P1") (pintype "bidirectional"))
    )
    (net (code "39") (name "Net-(S1-1)") (class "Default")
      (node (ref "R1") (pin "1") (pinfunction "1_1") (pintype "passive"))
      (node (ref "S1") (pin "P1-TA") (pinfunction "1_P1-TA") (pintype "bidirectional"))
      (node (ref "S1") (pin "P2-TB") (pinfunction "6_P2-TB") (pintype "bidirectional"))
    )
    (net (code "40") (name "Net-(S1-3)") (class "Default")
      (node (ref "R2") (pin "1") (pinfunction "1_1") (pintype "passive"))
      (node (ref "S1") (pin "P1-TB") (pinfunction "3_P1-TB") (pintype "bidirectional"))
      (node (ref "S1") (pin "P2-TA") (pinfunction "4_P2-TA") (pintype "bidirectional"))
    )
    (net (code "41") (name "Net-(U1A--IN)") (class "Default")
      (node (ref "R7") (pin "1") (pinfunction "1_1") (pintype "passive"))
      (node (ref "U1") (pin "1") (pinfunction "OUT_1") (pintype "output"))
      (node (ref "U1") (pin "2") (pinfunction "-IN_2") (pintype "input"))
    )
    (net (code "42") (name "Net-(U1B-+IN)") (class "Default")
      (node (ref "R5") (pin "2") (pinfunction "2_2") (pintype "passive"))
      (node (ref "R6") (pin "2") (pinfunction "2_2") (pintype "passive"))
      (node (ref "U1") (pin "5") (pinfunction "+IN_5") (pintype "input"))
    )
    (net (code "43") (name "Net-(U1C-+IN)") (class "Default")
      (node (ref "R8") (pin "2") (pinfunction "2_2") (pintype "passive"))
      (node (ref "R9") (pin "2") (pinfunction "2_2") (pintype "passive"))
      (node (ref "U1") (pin "10") (pinfunction "+IN_10") (pintype "input"))
    )
    (net (code "44") (name "Net-(U1D--IN)") (class "Default")
      (node (ref "R12") (pin "1") (pinfunction "1_1") (pintype "passive"))
      (node (ref "U1") (pin "13") (pinfunction "-IN_13") (pintype "input"))
      (node (ref "U1") (pin "14") (pinfunction "OUT_14") (pintype "output"))
    )
    (net (code "45") (name "Net-(U2A--IN)") (class "Default")
      (node (ref "R52") (pin "1") (pinfunction "1_1") (pintype "passive"))
      (node (ref "U2") (pin "1") (pinfunction "OUT_1") (pintype "output"))
      (node (ref "U2") (pin "2") (pinfunction "-IN_2") (pintype "input"))
    )
    (net (code "46") (name "Net-(U2B-+IN)") (class "Default")
      (node (ref "R10") (pin "2") (pinfunction "2_2") (pintype "passive"))
      (node (ref "R11") (pin "2") (pinfunction "2_2") (pintype "passive"))
      (node (ref "U2") (pin "5") (pinfunction "+IN_5") (pintype "input"))
    )
    (net (code "47") (name "Net-(U2C-+IN)") (class "Default")
      (node (ref "R13") (pin "2") (pinfunction "2_2") (pintype "passive"))
      (node (ref "R14") (pin "2") (pinfunction "2_2") (pintype "passive"))
      (node (ref "U2") (pin "10") (pinfunction "+IN_10") (pintype "input"))
    )
    (net (code "48") (name "Net-(U2D--IN)") (class "Default")
      (node (ref "R45") (pin "1") (pinfunction "1_1") (pintype "passive"))
      (node (ref "U2") (pin "13") (pinfunction "-IN_13") (pintype "input"))
      (node (ref "U2") (pin "14") (pinfunction "OUT_14") (pintype "output"))
    )
    (net (code "49") (name "Net-(U3A--IN)") (class "Default")
      (node (ref "R17") (pin "1") (pinfunction "1_1") (pintype "passive"))
      (node (ref "U3") (pin "1") (pinfunction "OUT_1") (pintype "output"))
      (node (ref "U3") (pin "2") (pinfunction "-IN_2") (pintype "input"))
    )
    (net (code "50") (name "Net-(U3B-+IN)") (class "Default")
      (node (ref "R15") (pin "2") (pinfunction "2_2") (pintype "passive"))
      (node (ref "R16") (pin "2") (pinfunction "2_2") (pintype "passive"))
      (node (ref "U3") (pin "5") (pinfunction "+IN_5") (pintype "input"))
    )
    (net (code "51") (name "Net-(U3C-+IN)") (class "Default")
      (node (ref "R18") (pin "2") (pinfunction "2_2") (pintype "passive"))
      (node (ref "R19") (pin "2") (pinfunction "2_2") (pintype "passive"))
      (node (ref "U3") (pin "10") (pinfunction "+IN_10") (pintype "input"))
    )
    (net (code "52") (name "Net-(U3D--IN)") (class "Default")
      (node (ref "R47") (pin "1") (pinfunction "1_1") (pintype "passive"))
      (node (ref "U3") (pin "13") (pinfunction "-IN_13") (pintype "input"))
      (node (ref "U3") (pin "14") (pinfunction "OUT_14") (pintype "output"))
    )
    (net (code "53") (name "Net-(U4A--IN)") (class "Default")
      (node (ref "R22") (pin "1") (pinfunction "1_1") (pintype "passive"))
      (node (ref "U4") (pin "1") (pinfunction "OUT_1") (pintype "output"))
      (node (ref "U4") (pin "2") (pinfunction "-IN_2") (pintype "input"))
    )
    (net (code "54") (name "Net-(U4B-+IN)") (class "Default")
      (node (ref "R20") (pin "2") (pinfunction "2_2") (pintype "passive"))
      (node (ref "R21") (pin "2") (pinfunction "2_2") (pintype "passive"))
      (node (ref "U4") (pin "5") (pinfunction "+IN_5") (pintype "input"))
    )
    (net (code "55") (name "Net-(U4C-+IN)") (class "Default")
      (node (ref "R23") (pin "2") (pinfunction "2_2") (pintype "passive"))
      (node (ref "R24") (pin "2") (pinfunction "2_2") (pintype "passive"))
      (node (ref "U4") (pin "10") (pinfunction "+IN_10") (pintype "input"))
    )
    (net (code "56") (name "Net-(U4D--IN)") (class "Default")
      (node (ref "R46") (pin "1") (pinfunction "1_1") (pintype "passive"))
      (node (ref "U4") (pin "13") (pinfunction "-IN_13") (pintype "input"))
      (node (ref "U4") (pin "14") (pinfunction "OUT_14") (pintype "output"))
    )
    (net (code "57") (name "Net-(U5A--IN)") (class "Default")
      (node (ref "R27") (pin "1") (pinfunction "1_1") (pintype "passive"))
      (node (ref "U5") (pin "1") (pinfunction "OUT_1") (pintype "output"))
      (node (ref "U5") (pin "2") (pinfunction "-IN_2") (pintype "input"))
    )
    (net (code "58") (name "Net-(U5B-+IN)") (class "Default")
      (node (ref "R25") (pin "2") (pinfunction "2_2") (pintype "passive"))
      (node (ref "R26") (pin "2") (pinfunction "2_2") (pintype "passive"))
      (node (ref "U5") (pin "5") (pinfunction "+IN_5") (pintype "input"))
    )
    (net (code "59") (name "Net-(U5C-+IN)") (class "Default")
      (node (ref "R28") (pin "2") (pinfunction "2_2") (pintype "passive"))
      (node (ref "R29") (pin "2") (pinfunction "2_2") (pintype "passive"))
      (node (ref "U5") (pin "10") (pinfunction "+IN_10") (pintype "input"))
    )
    (net (code "60") (name "Net-(U5D--IN)") (class "Default")
      (node (ref "R48") (pin "1") (pinfunction "1_1") (pintype "passive"))
      (node (ref "U5") (pin "13") (pinfunction "-IN_13") (pintype "input"))
      (node (ref "U5") (pin "14") (pinfunction "OUT_14") (pintype "output"))
    )
    (net (code "61") (name "Net-(U6A--IN)") (class "Default")
      (node (ref "R32") (pin "1") (pinfunction "1_1") (pintype "passive"))
      (node (ref "U6") (pin "1") (pinfunction "OUT_1") (pintype "output"))
      (node (ref "U6") (pin "2") (pinfunction "-IN_2") (pintype "input"))
    )
    (net (code "62") (name "Net-(U6B-+IN)") (class "Default")
      (node (ref "R30") (pin "2") (pinfunction "2_2") (pintype "passive"))
      (node (ref "R31") (pin "2") (pinfunction "2_2") (pintype "passive"))
      (node (ref "U6") (pin "5") (pinfunction "+IN_5") (pintype "input"))
    )
    (net (code "63") (name "Net-(U6C-+IN)") (class "Default")
      (node (ref "R33") (pin "2") (pinfunction "2_2") (pintype "passive"))
      (node (ref "R34") (pin "2") (pinfunction "2_2") (pintype "passive"))
      (node (ref "U6") (pin "10") (pinfunction "+IN_10") (pintype "input"))
    )
    (net (code "64") (name "Net-(U6D--IN)") (class "Default")
      (node (ref "R49") (pin "1") (pinfunction "1_1") (pintype "passive"))
      (node (ref "U6") (pin "13") (pinfunction "-IN_13") (pintype "input"))
      (node (ref "U6") (pin "14") (pinfunction "OUT_14") (pintype "output"))
    )
    (net (code "65") (name "Net-(U7A--IN)") (class "Default")
      (node (ref "R37") (pin "1") (pinfunction "1_1") (pintype "passive"))
      (node (ref "U7") (pin "1") (pinfunction "OUT_1") (pintype "output"))
      (node (ref "U7") (pin "2") (pinfunction "-IN_2") (pintype "input"))
    )
    (net (code "66") (name "Net-(U7B-+IN)") (class "Default")
      (node (ref "R35") (pin "2") (pinfunction "2_2") (pintype "passive"))
      (node (ref "R36") (pin "2") (pinfunction "2_2") (pintype "passive"))
      (node (ref "U7") (pin "5") (pinfunction "+IN_5") (pintype "input"))
    )
    (net (code "67") (name "Net-(U7C-+IN)") (class "Default")
      (node (ref "R38") (pin "2") (pinfunction "2_2") (pintype "passive"))
      (node (ref "R39") (pin "2") (pinfunction "2_2") (pintype "passive"))
      (node (ref "U7") (pin "10") (pinfunction "+IN_10") (pintype "input"))
    )
    (net (code "68") (name "Net-(U7D--IN)") (class "Default")
      (node (ref "R50") (pin "1") (pinfunction "1_1") (pintype "passive"))
      (node (ref "U7") (pin "13") (pinfunction "-IN_13") (pintype "input"))
      (node (ref "U7") (pin "14") (pinfunction "OUT_14") (pintype "output"))
    )
    (net (code "69") (name "Net-(U8A--IN)") (class "Default")
      (node (ref "R42") (pin "1") (pinfunction "1_1") (pintype "passive"))
      (node (ref "U8") (pin "1") (pinfunction "OUT_1") (pintype "output"))
      (node (ref "U8") (pin "2") (pinfunction "-IN_2") (pintype "input"))
    )
    (net (code "70") (name "Net-(U8B-+IN)") (class "Default")
      (node (ref "R40") (pin "2") (pinfunction "2_2") (pintype "passive"))
      (node (ref "R41") (pin "2") (pinfunction "2_2") (pintype "passive"))
      (node (ref "U8") (pin "5") (pinfunction "+IN_5") (pintype "input"))
    )
    (net (code "71") (name "Net-(U8C-+IN)") (class "Default")
      (node (ref "R43") (pin "2") (pinfunction "2_2") (pintype "passive"))
      (node (ref "R44") (pin "2") (pinfunction "2_2") (pintype "passive"))
      (node (ref "U8") (pin "10") (pinfunction "+IN_10") (pintype "input"))
    )
    (net (code "72") (name "Net-(U8D--IN)") (class "Default")
      (node (ref "R51") (pin "1") (pinfunction "1_1") (pintype "passive"))
      (node (ref "U8") (pin "13") (pinfunction "-IN_13") (pintype "input"))
      (node (ref "U8") (pin "14") (pinfunction "OUT_14") (pintype "output"))
    )
    (net (code "73") (name "SCL") (class "Default")
      (node (ref "D3") (pin "C") (pinfunction "C_C") (pintype "passive"))
      (node (ref "D4") (pin "A") (pinfunction "A_A") (pintype "passive"))
      (node (ref "JP2") (pin "RING") (pinfunction "RIGHT_RING") (pintype "bidirectional"))
      (node (ref "R4") (pin "1") (pinfunction "1_1") (pintype "passive"))
      (node (ref "U$1") (pin "29") (pinfunction "29/A18/SCL1_29") (pintype "bidirectional"))
    )
    (net (code "74") (name "SDA") (class "Default")
      (node (ref "D1") (pin "C") (pinfunction "C_C") (pintype "passive"))
      (node (ref "D2") (pin "A") (pinfunction "A_A") (pintype "passive"))
      (node (ref "JP2") (pin "TIP") (pinfunction "LEFT_TIP") (pintype "bidirectional"))
      (node (ref "R3") (pin "1") (pinfunction "1_1") (pintype "passive"))
      (node (ref "U$1") (pin "30") (pinfunction "30/A19/SDA1_30") (pintype "bidirectional"))
    )
    (net (code "75") (name "VBAT") (class "Default")
      (node (ref "U$1") (pin "VBAT") (pinfunction "VBAT_VBAT") (pintype "power_in"))
    )
    (net (code "76") (name "VIN") (class "Default")
      (node (ref "U$1") (pin "VIN") (pinfunction "VIN_VIN") (pintype "power_in"))
    )
    (net (code "77") (name "W0") (class "Default")
      (node (ref "R5") (pin "1") (pinfunction "1_1") (pintype "passive"))
      (node (ref "U$17") (pin "2") (pinfunction "2_2") (pintype "bidirectional"))
      (node (ref "U1") (pin "3") (pinfunction "+IN_3") (pintype "input"))
    )
    (net (code "78") (name "W1") (class "Default")
      (node (ref "R9") (pin "1") (pinfunction "1_1") (pintype "passive"))
      (node (ref "U$16") (pin "2") (pinfunction "2_2") (pintype "bidirectional"))
      (node (ref "U1") (pin "12") (pinfunction "+IN_12") (pintype "input"))
    )
    (net (code "79") (name "W2") (class "Default")
      (node (ref "R10") (pin "1") (pinfunction "1_1") (pintype "passive"))
      (node (ref "U$15") (pin "2") (pinfunction "2_2") (pintype "bidirectional"))
      (node (ref "U2") (pin "3") (pinfunction "+IN_3") (pintype "input"))
    )
    (net (code "80") (name "W3") (class "Default")
      (node (ref "R14") (pin "1") (pinfunction "1_1") (pintype "passive"))
      (node (ref "U$14") (pin "2") (pinfunction "2_2") (pintype "bidirectional"))
      (node (ref "U2") (pin "12") (pinfunction "+IN_12") (pintype "input"))
    )
    (net (code "81") (name "W4") (class "Default")
      (node (ref "R15") (pin "1") (pinfunction "1_1") (pintype "passive"))
      (node (ref "U$13") (pin "2") (pinfunction "2_2") (pintype "bidirectional"))
      (node (ref "U3") (pin "3") (pinfunction "+IN_3") (pintype "input"))
    )
    (net (code "82") (name "W5") (class "Default")
      (node (ref "R19") (pin "1") (pinfunction "1_1") (pintype "passive"))
      (node (ref "U$12") (pin "2") (pinfunction "2_2") (pintype "bidirectional"))
      (node (ref "U3") (pin "12") (pinfunction "+IN_12") (pintype "input"))
    )
    (net (code "83") (name "W6") (class "Default")
      (node (ref "R20") (pin "1") (pinfunction "1_1") (pintype "passive"))
      (node (ref "U$11") (pin "2") (pinfunction "2_2") (pintype "bidirectional"))
      (node (ref "U4") (pin "3") (pinfunction "+IN_3") (pintype "input"))
    )
    (net (code "84") (name "W7") (class "Default")
      (node (ref "R24") (pin "1") (pinfunction "1_1") (pintype "passive"))
      (node (ref "U$10") (pin "2") (pinfunction "2_2") (pintype "bidirectional"))
      (node (ref "U4") (pin "12") (pinfunction "+IN_12") (pintype "input"))
    )
    (net (code "85") (name "W8") (class "Default")
      (node (ref "R25") (pin "1") (pinfunction "1_1") (pintype "passive"))
      (node (ref "U$9") (pin "2") (pinfunction "2_2") (pintype "bidirectional"))
      (node (ref "U5") (pin "3") (pinfunction "+IN_3") (pintype "input"))
    )
    (net (code "86") (name "W9") (class "Default")
      (node (ref "R29") (pin "1") (pinfunction "1_1") (pintype "passive"))
      (node (ref "U$8") (pin "2") (pinfunction "2_2") (pintype "bidirectional"))
      (node (ref "U5") (pin "12") (pinfunction "+IN_12") (pintype "input"))
    )
    (net (code "87") (name "W10") (class "Default")
      (node (ref "R30") (pin "1") (pinfunction "1_1") (pintype "passive"))
      (node (ref "U$7") (pin "2") (pinfunction "2_2") (pintype "bidirectional"))
      (node (ref "U6") (pin "3") (pinfunction "+IN_3") (pintype "input"))
    )
    (net (code "88") (name "W11") (class "Default")
      (node (ref "R34") (pin "1") (pinfunction "1_1") (pintype "passive"))
      (node (ref "U$6") (pin "2") (pinfunction "2_2") (pintype "bidirectional"))
      (node (ref "U6") (pin "12") (pinfunction "+IN_12") (pintype "input"))
    )
    (net (code "89") (name "W12") (class "Default")
      (node (ref "R35") (pin "1") (pinfunction "1_1") (pintype "passive"))
      (node (ref "U$5") (pin "2") (pinfunction "2_2") (pintype "bidirectional"))
      (node (ref "U7") (pin "3") (pinfunction "+IN_3") (pintype "input"))
    )
    (net (code "90") (name "W13") (class "Default")
      (node (ref "R39") (pin "1") (pinfunction "1_1") (pintype "passive"))
      (node (ref "U$4") (pin "2") (pinfunction "2_2") (pintype "bidirectional"))
      (node (ref "U7") (pin "12") (pinfunction "+IN_12") (pintype "input"))
    )
    (net (code "91") (name "W14") (class "Default")
      (node (ref "R40") (pin "1") (pinfunction "1_1") (pintype "passive"))
      (node (ref "U$3") (pin "2") (pinfunction "2_2") (pintype "bidirectional"))
      (node (ref "U8") (pin "3") (pinfunction "+IN_3") (pintype "input"))
    )
    (net (code "92") (name "W15") (class "Default")
      (node (ref "R44") (pin "1") (pinfunction "1_1") (pintype "passive"))
      (node (ref "U$2") (pin "2") (pinfunction "2_2") (pintype "bidirectional"))
      (node (ref "U8") (pin "12") (pinfunction "+IN_12") (pintype "input"))
    )
    (net (code "93") (name "unconnected-(J1-SWITCH-PadSW)") (class "Default")
      (node (ref "J1") (pin "SW") (pinfunction "SWITCH_SW") (pintype "passive"))
    )
    (net (code "94") (name "unconnected-(J2-SWITCH-PadSW)") (class "Default")
      (node (ref "J2") (pin "SW") (pinfunction "SWITCH_SW") (pintype "passive"))
    )
    (net (code "95") (name "unconnected-(J3-SWITCH-PadSW)") (class "Default")
      (node (ref "J3") (pin "SW") (pinfunction "SWITCH_SW") (pintype "passive"))
    )
    (net (code "96") (name "unconnected-(J4-SWITCH-PadSW)") (class "Default")
      (node (ref "J4") (pin "SW") (pinfunction "SWITCH_SW") (pintype "passive"))
    )
    (net (code "97") (name "unconnected-(J5-SWITCH-PadSW)") (class "Default")
      (node (ref "J5") (pin "SW") (pinfunction "SWITCH_SW") (pintype "passive"))
    )
    (net (code "98") (name "unconnected-(J6-SWITCH-PadSW)") (class "Default")
      (node (ref "J6") (pin "SW") (pinfunction "SWITCH_SW") (pintype "passive"))
    )
    (net (code "99") (name "unconnected-(J7-SWITCH-PadSW)") (class "Default")
      (node (ref "J7") (pin "SW") (pinfunction "SWITCH_SW") (pintype "passive"))
    )
    (net (code "100") (name "unconnected-(J8-SWITCH-PadSW)") (class "Default")
      (node (ref "J8") (pin "SW") (pinfunction "SWITCH_SW") (pintype "passive"))
    )
    (net (code "101") (name "unconnected-(J9-SWITCH-PadSW)") (class "Default")
      (node (ref "J9") (pin "SW") (pinfunction "SWITCH_SW") (pintype "passive"))
    )
    (net (code "102") (name "unconnected-(J10-SWITCH-PadSW)") (class "Default")
      (node (ref "J10") (pin "SW") (pinfunction "SWITCH_SW") (pintype "passive"))
    )
    (net (code "103") (name "unconnected-(J11-SWITCH-PadSW)") (class "Default")
      (node (ref "J11") (pin "SW") (pinfunction "SWITCH_SW") (pintype "passive"))
    )
    (net (code "104") (name "unconnected-(J12-SWITCH-PadSW)") (class "Default")
      (node (ref "J12") (pin "SW") (pinfunction "SWITCH_SW") (pintype "passive"))
    )
    (net (code "105") (name "unconnected-(J13-SWITCH-PadSW)") (class "Default")
      (node (ref "J13") (pin "SW") (pinfunction "SWITCH_SW") (pintype "passive"))
    )
    (net (code "106") (name "unconnected-(J14-SWITCH-PadSW)") (class "Default")
      (node (ref "J14") (pin "SW") (pinfunction "SWITCH_SW") (pintype "passive"))
    )
    (net (code "107") (name "unconnected-(J15-SWITCH-PadSW)") (class "Default")
      (node (ref "J15") (pin "SW") (pinfunction "SWITCH_SW") (pintype "passive"))
    )
    (net (code "108") (name "unconnected-(J16-SWITCH-PadSW)") (class "Default")
      (node (ref "J16") (pin "SW") (pinfunction "SWITCH_SW") (pintype "passive"))
    )
    (net (code "109") (name "unconnected-(U$1-0{slash}RX1{slash}T-Pad0)") (class "Default")
      (node (ref "U$1") (pin "0") (pinfunction "0/RX1/T_0") (pintype "bidirectional"))
    )
    (net (code "110") (name "unconnected-(U$1-3{slash}CAN-TX{slash}PWM-Pad3)") (class "Default")
      (node (ref "U$1") (pin "3") (pinfunction "3/CAN-TX/PWM_3") (pintype "bidirectional"))
    )
    (net (code "111") (name "unconnected-(U$1-4{slash}CAN-RX-PWM-Pad4)") (class "Default")
      (node (ref "U$1") (pin "4") (pinfunction "4/CAN-RX-PWM_4") (pintype "bidirectional"))
    )
    (net (code "112") (name "unconnected-(U$1-5{slash}PWM-Pad5)") (class "Default")
      (node (ref "U$1") (pin "5") (pinfunction "5/PWM_5") (pintype "bidirectional"))
    )
    (net (code "113") (name "unconnected-(U$1-6{slash}PWM-Pad6)") (class "Default")
      (node (ref "U$1") (pin "6") (pinfunction "6/PWM_6") (pintype "bidirectional"))
    )
    (net (code "114") (name "unconnected-(U$1-7{slash}RX3-Pad7)") (class "Default")
      (node (ref "U$1") (pin "7") (pinfunction "7/RX3_7") (pintype "bidirectional"))
    )
    (net (code "115") (name "unconnected-(U$1-8{slash}TX3-Pad8)") (class "Default")
      (node (ref "U$1") (pin "8") (pinfunction "8/TX3_8") (pintype "bidirectional"))
    )
    (net (code "116") (name "unconnected-(U$1-9{slash}RX2{slash}PWM-Pad9)") (class "Default")
      (node (ref "U$1") (pin "9") (pinfunction "9/RX2/PWM_9") (pintype "bidirectional"))
    )
    (net (code "117") (name "unconnected-(U$1-10{slash}TX2{slash}PWM-Pad10)") (class "Default")
      (node (ref "U$1") (pin "10") (pinfunction "10/TX2/PWM_10") (pintype "bidirectional"))
    )
    (net (code "118") (name "unconnected-(U$1-11{slash}MOSI-Pad11)") (class "Default")
      (node (ref "U$1") (pin "11") (pinfunction "11/MOSI_11") (pintype "bidirectional"))
    )
    (net (code "119") (name "unconnected-(U$1-12{slash}MISO-Pad12)") (class "Default")
      (node (ref "U$1") (pin "12") (pinfunction "12/MISO_12") (pintype "bidirectional"))
    )
    (net (code "120") (name "unconnected-(U$1-13{slash}SCK{slash}LED-Pad13)") (class "Default")
      (node (ref "U$1") (pin "13") (pinfunction "13/SCK/LED_13") (pintype "bidirectional"))
    )
    (net (code "121") (name "unconnected-(U$1-25{slash}T{slash}PWM-Pad25)") (class "Default")
      (node (ref "U$1") (pin "25") (pinfunction "25/T/PWM_25") (pintype "bidirectional"))
    )
    (net (code "122") (name "unconnected-(U$1-27{slash}A16-Pad27)") (class "Default")
      (node (ref "U$1") (pin "27") (pinfunction "27/A16_27") (pintype "bidirectional"))
    )
    (net (code "123") (name "unconnected-(U$1-28{slash}A17-Pad28)") (class "Default")
      (node (ref "U$1") (pin "28") (pinfunction "28/A17_28") (pintype "bidirectional"))
    )
    (net (code "124") (name "unconnected-(U$1-31{slash}A20-Pad31)") (class "Default")
      (node (ref "U$1") (pin "31") (pinfunction "31/A20_31") (pintype "bidirectional"))
    )
    (net (code "125") (name "unconnected-(U$1-32{slash}T{slash}PWM-Pad32)") (class "Default")
      (node (ref "U$1") (pin "32") (pinfunction "32/T/PWM_32") (pintype "bidirectional"))
    )
    (net (code "126") (name "unconnected-(U$1-33{slash}T-Pad33)") (class "Default")
      (node (ref "U$1") (pin "33") (pinfunction "33/T_33") (pintype "bidirectional"))
    )
    (net (code "127") (name "unconnected-(U$1-Pad2)") (class "Default")
      (node (ref "U$1") (pin "2") (pinfunction "2_2") (pintype "bidirectional"))
    )
    (net (code "128") (name "unconnected-(U$1-Pad24)") (class "Default")
      (node (ref "U$1") (pin "24") (pinfunction "24_24") (pintype "bidirectional"))
    )
    (net (code "129") (name "unconnected-(U$1-PadPGM)") (class "Default")
      (node (ref "U$1") (pin "PGM") (pinfunction "PGM_PGM") (pintype "bidirectional"))
    )
  )
)
